# max1551_charger_v1.net
KiCad netlist of a schematic drawn in EAGLE
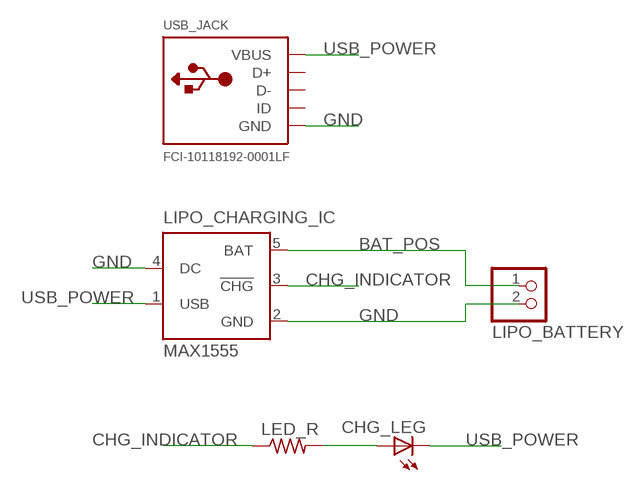
[diagram p0: schematic, sheet 1]

(export (version "E")
  (design (tool "Eeschema 10.0.6"))
  (components
    (comp (ref "CHG_LEG")
      (value "LED3MM")
      (footprint "eagle-import:LED3MM")
      (libsource (lib "eagle-import") (part "LED3MM"))
    )
    (comp (ref "LED_R")
      (value "R-US_0207/2V")
      (footprint "eagle-import:0207_2V")
      (libsource (lib "eagle-import") (part "R-US_0207/2V"))
    )
    (comp (ref "LIPO_BATTERY")
      (value "JST_2PIN-SMT-RA")
      (footprint "eagle-import:JST-PH-2-SMT-RA")
      (libsource (lib "eagle-import") (part "JST_2PIN-SMT-RA"))
    )
    (comp (ref "LIPO_CHARGING_IC")
      (value "MAX1555")
      (footprint "eagle-import:SOT23-5L")
      (fields (field (name "MF") "MAXIM") (field (name "MPN") "MAX1555EZK+T"))
      (libsource (lib "eagle-import") (part "MAX1555"))
    )
    (comp (ref "USB_JACK")
      (value "FCI-10118192-0001LF")
      (footprint "eagle-import:FCI-10118192-0001LF")
      (libsource (lib "eagle-import") (part "FCI-10118192-0001LF"))
    )
  )
  (nets
    (net (code "1") (name "/BAT_POS") (class "Default")
      (node (ref "LIPO_BATTERY") (pin "1") (pinfunction "2_1") (pintype "passive"))
      (node (ref "LIPO_CHARGING_IC") (pin "5") (pinfunction "BAT_5") (pintype "passive"))
    )
    (net (code "2") (name "/CHG_INDICATOR") (class "Default")
      (node (ref "LED_R") (pin "1") (pinfunction "1_1") (pintype "passive"))
      (node (ref "LIPO_CHARGING_IC") (pin "3") (pinfunction "~{CHG}_3") (pintype "output"))
    )
    (net (code "3") (name "/GND") (class "Default")
      (node (ref "LIPO_BATTERY") (pin "2") (pinfunction "1_2") (pintype "passive"))
      (node (ref "LIPO_CHARGING_IC") (pin "2") (pinfunction "GND_2") (pintype "power_in"))
      (node (ref "LIPO_CHARGING_IC") (pin "4") (pinfunction "DC_4") (pintype "input"))
      (node (ref "USB_JACK") (pin "GND") (pinfunction "GND_GND") (pintype "power_in"))
    )
    (net (code "4") (name "/USB_POWER") (class "Default")
      (node (ref "CHG_LEG") (pin "K") (pinfunction "C_K") (pintype "passive"))
      (node (ref "LIPO_CHARGING_IC") (pin "1") (pinfunction "USB_1") (pintype "input"))
      (node (ref "USB_JACK") (pin "VCC") (pinfunction "VBUS_VCC") (pintype "power_in"))
    )
    (net (code "5") (name "Net-(CHG_LEG-PadA)") (class "Default")
      (node (ref "CHG_LEG") (pin "A") (pinfunction "A_A") (pintype "passive"))
      (node (ref "LED_R") (pin "2") (pinfunction "2_2") (pintype "passive"))
    )
    (net (code "6") (name "unconnected-(USB_JACK-D+-PadRX)") (class "Default")
      (node (ref "USB_JACK") (pin "RX") (pinfunction "D+_RX") (pintype "bidirectional"))
    )
    (net (code "7") (name "unconnected-(USB_JACK-D--PadTX)") (class "Default")
      (node (ref "USB_JACK") (pin "TX") (pinfunction "D-_TX") (pintype "bidirectional"))
    )
    (net (code "8") (name "unconnected-(USB_JACK-ID-PadNC@0)") (class "Default")
      (node (ref "USB_JACK") (pin "NC@0") (pinfunction "ID_NC@0") (pintype "bidirectional"))
    )
  )
)
